# power.net
KiCad netlist of a schematic drawn in Altium Designer
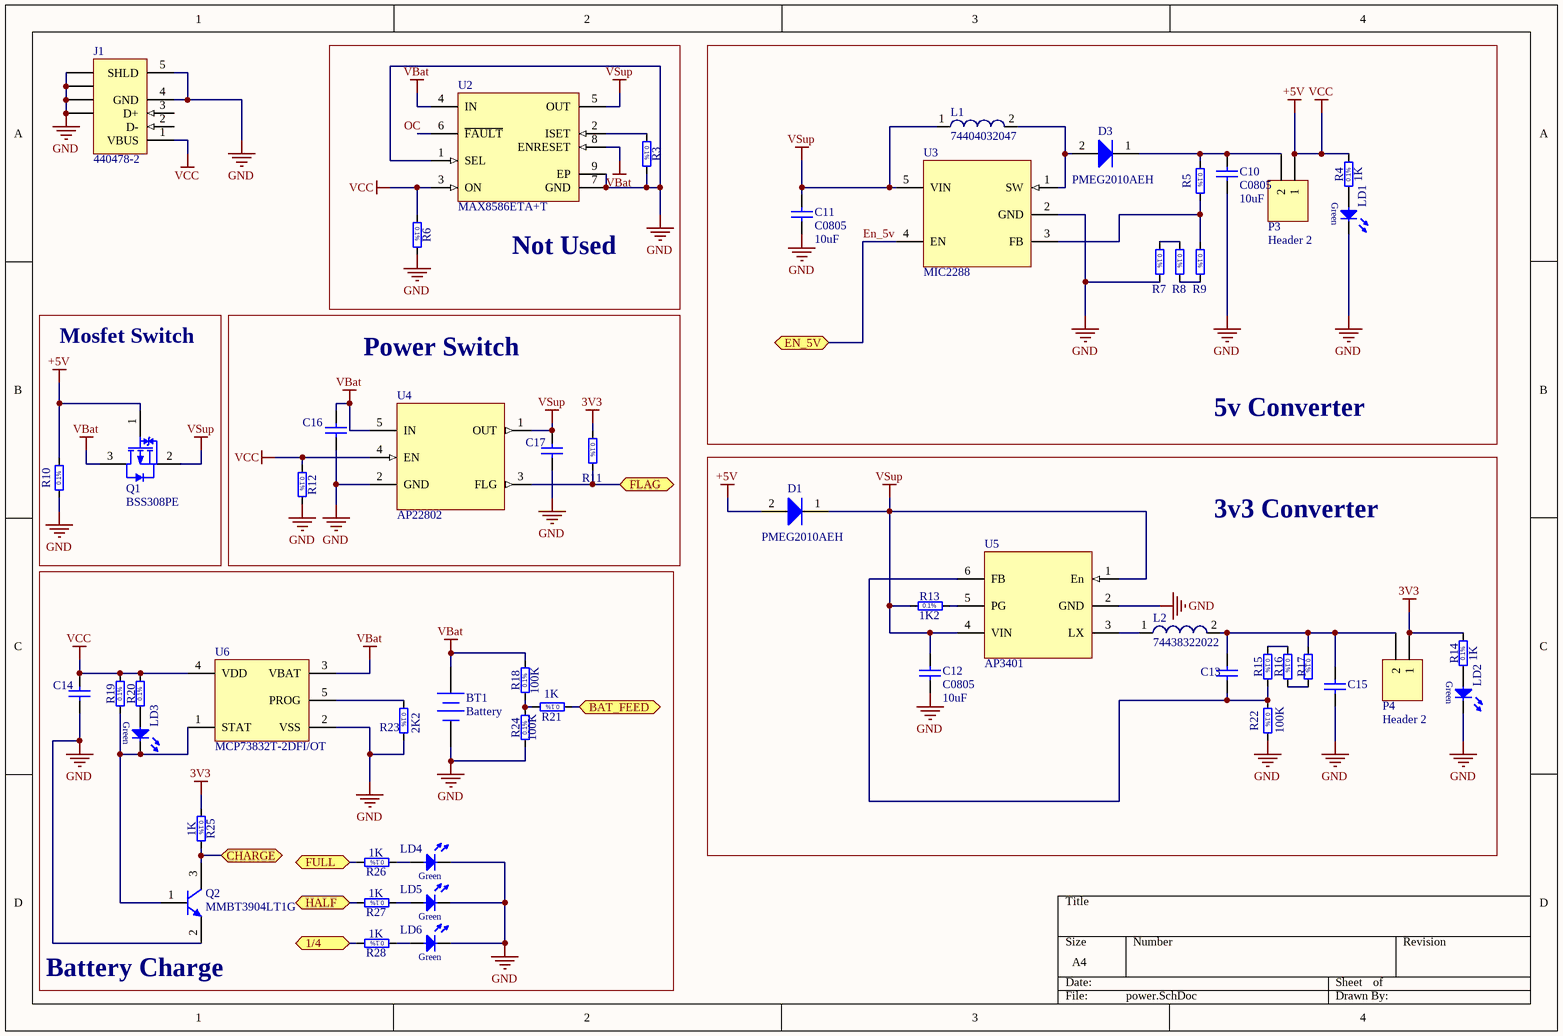
[diagram p0: power.SchDoc]

(export (version "E")
  (design (tool "Eeschema 10.0.6"))
  (components
    (comp (ref "BT1")
      (value "Battery")
      (footprint "BAT-2")
      (description "Multicell Battery")
      (fields (field (name "PUBLISHER") "Altium Limited"))
      (libsource (lib "Miscellaneous Devices") (part "Battery"))
    )
    (comp (ref "C10")
      (value "C0805")
      (footprint "0805")
      (description "Ceramic Chip Capacitor - Standard")
      (fields (field (name "ALTIUM_VALUE") "10uF") (field (name "PUBLISHER") "Altium Limited"))
      (libsource (lib "KEMET Chip Capacitor") (part "C0805"))
    )
    (comp (ref "C11")
      (value "C0805")
      (footprint "0805")
      (description "Ceramic Chip Capacitor - Standard")
      (fields (field (name "ALTIUM_VALUE") "10uF") (field (name "PUBLISHER") "Altium Limited"))
      (libsource (lib "KEMET Chip Capacitor") (part "C0805"))
    )
    (comp (ref "C12")
      (value "C0805")
      (footprint "0805")
      (description "Ceramic Chip Capacitor - Standard")
      (fields (field (name "ALTIUM_VALUE") "10uF") (field (name "PUBLISHER") "Altium Limited"))
      (libsource (lib "KEMET Chip Capacitor") (part "C0805"))
    )
    (comp (ref "C13")
      (value "C0805")
      (footprint "0805")
      (description "Ceramic Chip Capacitor - Standard")
      (fields (field (name "PUBLISHER") "Altium Limited"))
      (libsource (lib "KEMET Chip Capacitor") (part "C0805"))
    )
    (comp (ref "C14")
      (value "C0805")
      (footprint "0805")
      (description "Ceramic Chip Capacitor - Standard")
      (fields (field (name "PUBLISHER") "Altium Limited"))
      (libsource (lib "KEMET Chip Capacitor") (part "C0805"))
    )
    (comp (ref "C15")
      (value "C0805")
      (footprint "0805")
      (description "Ceramic Chip Capacitor - Standard")
      (fields (field (name "PUBLISHER") "Altium Limited"))
      (libsource (lib "KEMET Chip Capacitor") (part "C0805"))
    )
    (comp (ref "C16")
      (value "C0805")
      (footprint "0805")
      (description "Ceramic Chip Capacitor - Standard")
      (fields (field (name "PUBLISHER") "Altium Limited"))
      (libsource (lib "KEMET Chip Capacitor") (part "C0805"))
    )
    (comp (ref "C17")
      (value "C0805")
      (footprint "0805")
      (description "Ceramic Chip Capacitor - Standard")
      (fields (field (name "PUBLISHER") "Altium Limited"))
      (libsource (lib "KEMET Chip Capacitor") (part "C0805"))
    )
    (comp (ref "D1")
      (value "PMEG2010AEH")
      (footprint "ONSC-SOD-123-2-425-04_V")
      (description "Switching Diode, 2-Pin SOD-123, Pb-Free, Tape and Reel")
      (fields (field (name "MANUFACTURER") "On Semiconductor") (field (name "PARTNUMBER") "MMSD914T3G"))
      (libsource (lib "ON Semi Small Signal Switching Diodes") (part "MMSD914T3G"))
    )
    (comp (ref "D3")
      (value "PMEG2010AEH")
      (footprint "ONSC-SOD-123-2-425-04_V")
      (description "Switching Diode, 2-Pin SOD-123, Pb-Free, Tape and Reel")
      (fields (field (name "MANUFACTURER") "On Semiconductor") (field (name "PARTNUMBER") "MMSD914T3G"))
      (libsource (lib "ON Semi Small Signal Switching Diodes") (part "MMSD914T3G"))
    )
    (comp (ref "J1")
      (value "440478-2")
      (footprint "440478")
      (description "USB 2.0, Right Angle, SMT, A Type, Receptacle, 5 Position, Black")
      (fields (field (name "PUBLISHER") "Altium Limited"))
      (libsource (lib "AMP Serial Bus USB") (part "440478-2"))
    )
    (comp (ref "L1")
      (value "74404032047")
      (footprint "WE-LQS 3015")
      (description "WE-LQS SMD Power Inductor, L=4.7 µH")
      (libsource (lib "WE-LQS SMD Power Inductor") (part "74404032047"))
    )
    (comp (ref "L2")
      (value "74438322022")
      (footprint "SMD 2508")
      (description "Power Multilayer Inductor WE-MAPI, L=2.2µH")
      (libsource (lib "WE-MAPI SMD Power Inductor") (part "74438322022"))
    )
    (comp (ref "LD1")
      (value "Green")
      (footprint "LED_OSRAM_LGR971")
      (description "LED Green 1C 2A")
      (fields
        (field (name "PART NUMBER") "LED_OSRAM_LGR971")
        (field (name "MANUFACTURER") "OSRAM")
        (field (name "AUTHOR") "CERN DEM JLC")
      )
      (libsource (lib "ICs And Semiconductors") (part "LED Green 1C 2A"))
    )
    (comp (ref "LD2")
      (value "Green")
      (footprint "LED_OSRAM_LGR971")
      (description "LED Green 1C 2A")
      (fields
        (field (name "PART NUMBER") "LED_OSRAM_LGR971")
        (field (name "MANUFACTURER") "OSRAM")
        (field (name "AUTHOR") "CERN DEM JLC")
      )
      (libsource (lib "ICs And Semiconductors") (part "LED Green 1C 2A"))
    )
    (comp (ref "LD3")
      (value "Green")
      (footprint "LED_OSRAM_LGR971")
      (description "LED Green 1C 2A")
      (fields
        (field (name "PART NUMBER") "LED_OSRAM_LGR971")
        (field (name "MANUFACTURER") "OSRAM")
        (field (name "AUTHOR") "CERN DEM JLC")
      )
      (libsource (lib "ICs And Semiconductors") (part "LED Green 1C 2A"))
    )
    (comp (ref "LD4")
      (value "Green")
      (footprint "LED_OSRAM_LGR971")
      (description "LED Green 1C 2A")
      (fields
        (field (name "PART NUMBER") "LED_OSRAM_LGR971")
        (field (name "MANUFACTURER") "OSRAM")
        (field (name "AUTHOR") "CERN DEM JLC")
      )
      (libsource (lib "ICs And Semiconductors") (part "LED Green 1C 2A"))
    )
    (comp (ref "LD5")
      (value "Green")
      (footprint "LED_OSRAM_LGR971")
      (description "LED Green 1C 2A")
      (fields
        (field (name "PART NUMBER") "LED_OSRAM_LGR971")
        (field (name "MANUFACTURER") "OSRAM")
        (field (name "AUTHOR") "CERN DEM JLC")
      )
      (libsource (lib "ICs And Semiconductors") (part "LED Green 1C 2A"))
    )
    (comp (ref "LD6")
      (value "Green")
      (footprint "LED_OSRAM_LGR971")
      (description "LED Green 1C 2A")
      (fields
        (field (name "PART NUMBER") "LED_OSRAM_LGR971")
        (field (name "MANUFACTURER") "OSRAM")
        (field (name "AUTHOR") "CERN DEM JLC")
      )
      (libsource (lib "ICs And Semiconductors") (part "LED Green 1C 2A"))
    )
    (comp (ref "P3")
      (value "Header 2")
      (footprint "HDR1X2")
      (description "Header, 2-Pin")
      (fields (field (name "PUBLISHER") "Altium Limited"))
      (libsource (lib "Miscellaneous Connectors") (part "Header 2"))
    )
    (comp (ref "P4")
      (value "Header 2")
      (footprint "HDR1X2")
      (description "Header, 2-Pin")
      (fields (field (name "PUBLISHER") "Altium Limited"))
      (libsource (lib "Miscellaneous Connectors") (part "Header 2"))
    )
    (comp (ref "Q1")
      (value "BSS308PE")
      (footprint "INF-PG-SOT23_N")
      (fields (field (name "MANUFACTURER") "Infineon"))
      (libsource (lib "Infineon Power MOSFET") (part "BSS308PE"))
    )
    (comp (ref "Q2")
      (value "MMBT3904LT1G")
      (footprint "ONSC-SOT-23-3-318-08_V")
      (description "General Purpose Transistor, NPN Silicon, 3-Pin SOT-23, Pb-Free, Tape and Reel")
      (fields (field (name "MANUFACTURER") "On Semiconductor"))
      (libsource (lib "ON Semi General Purpose Transistors") (part "MMBT3904LT1G"))
    )
    (comp (ref "R3")
      (value "26K")
      (footprint "RESC2012X60N")
      (description "Resistor - 0.1%")
      (fields
        (field (name "PART NUMBER") "R0805_1K1_0.1%_0.1W_10PPM")
        (field (name "POWER") "0.1W")
        (field (name "AUTHOR") "CERN DEM JLC")
      )
      (libsource (lib "Resistors") (part "Resistor - 0.1%"))
    )
    (comp (ref "R4")
      (value "1K")
      (footprint "RESC2012X60N")
      (description "Resistor - 0.1%")
      (fields
        (field (name "PART NUMBER") "R0805_1K1_0.1%_0.1W_10PPM")
        (field (name "POWER") "0.1W")
        (field (name "AUTHOR") "CERN DEM JLC")
      )
      (libsource (lib "Resistors") (part "Resistor - 0.1%"))
    )
    (comp (ref "R5")
      (value "100K")
      (footprint "RESC2012X60N")
      (description "Resistor - 0.1%")
      (fields
        (field (name "PART NUMBER") "R0805_1K1_0.1%_0.1W_10PPM")
        (field (name "POWER") "0.1W")
        (field (name "AUTHOR") "CERN DEM JLC")
      )
      (libsource (lib "Resistors") (part "Resistor - 0.1%"))
    )
    (comp (ref "R6")
      (value "1K2")
      (footprint "RESC2012X60N")
      (description "Resistor - 0.1%")
      (fields
        (field (name "PART NUMBER") "R0805_1K1_0.1%_0.1W_10PPM")
        (field (name "POWER") "0.1W")
        (field (name "AUTHOR") "CERN DEM JLC")
      )
      (libsource (lib "Resistors") (part "Resistor - 0.1%"))
    )
    (comp (ref "R7")
      (value "10K")
      (footprint "RESC2012X60N")
      (description "Resistor - 0.1%")
      (fields
        (field (name "PART NUMBER") "R0805_1K1_0.1%_0.1W_10PPM")
        (field (name "POWER") "0.1W")
        (field (name "AUTHOR") "CERN DEM JLC")
      )
      (libsource (lib "Resistors") (part "Resistor - 0.1%"))
    )
    (comp (ref "R8")
      (value "1K")
      (footprint "RESC2012X60N")
      (description "Resistor - 0.1%")
      (fields
        (field (name "PART NUMBER") "R0805_1K1_0.1%_0.1W_10PPM")
        (field (name "POWER") "0.1W")
        (field (name "AUTHOR") "CERN DEM JLC")
      )
      (libsource (lib "Resistors") (part "Resistor - 0.1%"))
    )
    (comp (ref "R9")
      (value "100R")
      (footprint "RESC2012X60N")
      (description "Resistor - 0.1%")
      (fields
        (field (name "PART NUMBER") "R0805_1K1_0.1%_0.1W_10PPM")
        (field (name "POWER") "0.1W")
        (field (name "AUTHOR") "CERN DEM JLC")
      )
      (libsource (lib "Resistors") (part "Resistor - 0.1%"))
    )
    (comp (ref "R10")
      (value "1K2")
      (footprint "RESC2012X60N")
      (description "Resistor - 0.1%")
      (fields
        (field (name "PART NUMBER") "R0805_1K1_0.1%_0.1W_10PPM")
        (field (name "POWER") "0.1W")
        (field (name "AUTHOR") "CERN DEM JLC")
      )
      (libsource (lib "Resistors") (part "Resistor - 0.1%"))
    )
    (comp (ref "R11")
      (value "10K")
      (footprint "RESC2012X60N")
      (description "Resistor - 0.1%")
      (fields
        (field (name "PART NUMBER") "R0805_1K1_0.1%_0.1W_10PPM")
        (field (name "POWER") "0.1W")
        (field (name "AUTHOR") "CERN DEM JLC")
      )
      (libsource (lib "Resistors") (part "Resistor - 0.1%"))
    )
    (comp (ref "R12")
      (value "1K2")
      (footprint "RESC2012X60N")
      (description "Resistor - 0.1%")
      (fields
        (field (name "PART NUMBER") "R0805_1K1_0.1%_0.1W_10PPM")
        (field (name "POWER") "0.1W")
        (field (name "AUTHOR") "CERN DEM JLC")
      )
      (libsource (lib "Resistors") (part "Resistor - 0.1%"))
    )
    (comp (ref "R13")
      (value "1K2")
      (footprint "RESC2012X60N")
      (description "Resistor - 0.1%")
      (fields
        (field (name "PART NUMBER") "R0805_1K1_0.1%_0.1W_10PPM")
        (field (name "POWER") "0.1W")
        (field (name "AUTHOR") "CERN DEM JLC")
      )
      (libsource (lib "Resistors") (part "Resistor - 0.1%"))
    )
    (comp (ref "R14")
      (value "1K")
      (footprint "RESC2012X60N")
      (description "Resistor - 0.1%")
      (fields
        (field (name "PART NUMBER") "R0805_1K1_0.1%_0.1W_10PPM")
        (field (name "POWER") "0.1W")
        (field (name "AUTHOR") "CERN DEM JLC")
      )
      (libsource (lib "Resistors") (part "Resistor - 0.1%"))
    )
    (comp (ref "R15")
      (value "RC0805FR-07430KL")
      (footprint "RESC2012X60N")
      (description "Resistor - 0.1%")
      (fields
        (field (name "PART NUMBER") "R0805_1K1_0.1%_0.1W_10PPM")
        (field (name "POWER") "0.1W")
        (field (name "AUTHOR") "CERN DEM JLC")
      )
      (libsource (lib "Resistors") (part "Resistor - 0.1%"))
    )
    (comp (ref "R16")
      (value "150K")
      (footprint "RESC2012X60N")
      (description "Resistor - 0.1%")
      (fields
        (field (name "PART NUMBER") "R0805_1K1_0.1%_0.1W_10PPM")
        (field (name "POWER") "0.1W")
        (field (name "AUTHOR") "CERN DEM JLC")
      )
      (libsource (lib "Resistors") (part "Resistor - 0.1%"))
    )
    (comp (ref "R17")
      (value "150K")
      (footprint "RESC2012X60N")
      (description "Resistor - 0.1%")
      (fields
        (field (name "PART NUMBER") "R0805_1K1_0.1%_0.1W_10PPM")
        (field (name "POWER") "0.1W")
        (field (name "AUTHOR") "CERN DEM JLC")
      )
      (libsource (lib "Resistors") (part "Resistor - 0.1%"))
    )
    (comp (ref "R18")
      (value "100K")
      (footprint "RESC2012X60N")
      (description "Resistor - 0.1%")
      (fields
        (field (name "PART NUMBER") "R0805_1K1_0.1%_0.1W_10PPM")
        (field (name "POWER") "0.1W")
        (field (name "AUTHOR") "CERN DEM JLC")
      )
      (libsource (lib "Resistors") (part "Resistor - 0.1%"))
    )
    (comp (ref "R19")
      (value "1K")
      (footprint "RESC2012X60N")
      (description "Resistor - 0.1%")
      (fields
        (field (name "PART NUMBER") "R0805_1K1_0.1%_0.1W_10PPM")
        (field (name "POWER") "0.1W")
        (field (name "AUTHOR") "CERN DEM JLC")
      )
      (libsource (lib "Resistors") (part "Resistor - 0.1%"))
    )
    (comp (ref "R20")
      (value "1K")
      (footprint "RESC2012X60N")
      (description "Resistor - 0.1%")
      (fields
        (field (name "PART NUMBER") "R0805_1K1_0.1%_0.1W_10PPM")
        (field (name "POWER") "0.1W")
        (field (name "AUTHOR") "CERN DEM JLC")
      )
      (libsource (lib "Resistors") (part "Resistor - 0.1%"))
    )
    (comp (ref "R21")
      (value "1K")
      (footprint "RESC2012X60N")
      (description "Resistor - 0.1%")
      (fields
        (field (name "PART NUMBER") "R0805_1K1_0.1%_0.1W_10PPM")
        (field (name "POWER") "0.1W")
        (field (name "AUTHOR") "CERN DEM JLC")
      )
      (libsource (lib "Resistors") (part "Resistor - 0.1%"))
    )
    (comp (ref "R22")
      (value "100K")
      (footprint "RESC2012X60N")
      (description "Resistor - 0.1%")
      (fields
        (field (name "PART NUMBER") "R0805_1K1_0.1%_0.1W_10PPM")
        (field (name "POWER") "0.1W")
        (field (name "AUTHOR") "CERN DEM JLC")
      )
      (libsource (lib "Resistors") (part "Resistor - 0.1%"))
    )
    (comp (ref "R23")
      (value "2K2")
      (footprint "RESC2012X60N")
      (description "Resistor - 0.1%")
      (fields
        (field (name "PART NUMBER") "R0805_1K1_0.1%_0.1W_10PPM")
        (field (name "POWER") "0.1W")
        (field (name "AUTHOR") "CERN DEM JLC")
      )
      (libsource (lib "Resistors") (part "Resistor - 0.1%"))
    )
    (comp (ref "R24")
      (value "100K")
      (footprint "RESC2012X60N")
      (description "Resistor - 0.1%")
      (fields
        (field (name "PART NUMBER") "R0805_1K1_0.1%_0.1W_10PPM")
        (field (name "POWER") "0.1W")
        (field (name "AUTHOR") "CERN DEM JLC")
      )
      (libsource (lib "Resistors") (part "Resistor - 0.1%"))
    )
    (comp (ref "R25")
      (value "1K")
      (footprint "RESC2012X60N")
      (description "Resistor - 0.1%")
      (fields
        (field (name "PART NUMBER") "R0805_1K1_0.1%_0.1W_10PPM")
        (field (name "POWER") "0.1W")
        (field (name "AUTHOR") "CERN DEM JLC")
      )
      (libsource (lib "Resistors") (part "Resistor - 0.1%"))
    )
    (comp (ref "R26")
      (value "1K")
      (footprint "RESC2012X60N")
      (description "Resistor - 0.1%")
      (fields
        (field (name "PART NUMBER") "R0805_1K1_0.1%_0.1W_10PPM")
        (field (name "POWER") "0.1W")
        (field (name "AUTHOR") "CERN DEM JLC")
      )
      (libsource (lib "Resistors") (part "Resistor - 0.1%"))
    )
    (comp (ref "R27")
      (value "1K")
      (footprint "RESC2012X60N")
      (description "Resistor - 0.1%")
      (fields
        (field (name "PART NUMBER") "R0805_1K1_0.1%_0.1W_10PPM")
        (field (name "POWER") "0.1W")
        (field (name "AUTHOR") "CERN DEM JLC")
      )
      (libsource (lib "Resistors") (part "Resistor - 0.1%"))
    )
    (comp (ref "R28")
      (value "1K")
      (footprint "RESC2012X60N")
      (description "Resistor - 0.1%")
      (fields
        (field (name "PART NUMBER") "R0805_1K1_0.1%_0.1W_10PPM")
        (field (name "POWER") "0.1W")
        (field (name "AUTHOR") "CERN DEM JLC")
      )
      (libsource (lib "Resistors") (part "Resistor - 0.1%"))
    )
    (comp (ref "U2")
      (value "MAX8586ETA+T")
      (footprint "T833+2")
      (description "Single 1.2A USB Switch, 8-Pin TDFN, -40°C to +85°C, Pb-Free, Tape and Reel")
      (libsource (lib "Maxim Hot-Swap, PoE and Power Switching") (part "MAX8586ETA+T"))
    )
    (comp (ref "U3") (value "MIC2288") (footprint "TSOT25") (libsource (lib "Microchip") (part "MIC2288")))
    (comp (ref "U4")
      (value "AP22802")
      (footprint "TSOT25")
      (libsource (lib "Diodes Incorporated") (part "AP22802"))
    )
    (comp (ref "U5")
      (value "AP3401")
      (footprint "TSOT26")
      (libsource (lib "Diodes Incorporated") (part "AP3401"))
    )
    (comp (ref "U6")
      (value "MCP73832T-2DFI/OT")
      (footprint "SOT-23-OT5_N")
      (fields (field (name "MANUFACTURER") "Microchip"))
      (libsource (lib "Microchip Power Management Battery Management") (part "MCP73832T-2DFI/OT"))
    )
  )
  (nets
    (net (code "1") (name "+5V") (class "Default")
      (node (ref "C14") (pin "2") (pinfunction "2_2") (pintype "passive"))
      (node (ref "D1") (pin "2") (pinfunction "A_2") (pintype "passive"))
      (node (ref "J1") (pin "1") (pinfunction "VBUS_1") (pintype "power_in"))
      (node (ref "P3") (pin "1") (pinfunction "1_1") (pintype "passive"))
      (node (ref "Q1") (pin "1") (pinfunction "GATE_1") (pintype "passive"))
      (node (ref "R10") (pin "2") (pinfunction "2_2") (pintype "passive"))
      (node (ref "R12") (pin "1") (pinfunction "1_1") (pintype "passive"))
      (node (ref "R19") (pin "2") (pinfunction "2_2") (pintype "passive"))
      (node (ref "R20") (pin "2") (pinfunction "2_2") (pintype "passive"))
      (node (ref "R4") (pin "2") (pinfunction "2_2") (pintype "passive"))
      (node (ref "R6") (pin "1") (pinfunction "1_1") (pintype "passive"))
      (node (ref "U2") (pin "3") (pinfunction "ON_3") (pintype "input"))
      (node (ref "U4") (pin "4") (pinfunction "EN_4") (pintype "input"))
      (node (ref "U6") (pin "4") (pinfunction "VDD_4") (pintype "power_in"))
    )
    (net (code "2") (name "/1{slash}4") (class "Default")
      (node (ref "R28") (pin "2") (pinfunction "2_2") (pintype "passive"))
    )
    (net (code "3") (name "/BAT_FEED") (class "Default")
      (node (ref "R21") (pin "1") (pinfunction "1_1") (pintype "passive"))
    )
    (net (code "4") (name "/CHARGE") (class "Default")
      (node (ref "Q2") (pin "3") (pinfunction "C_3") (pintype "passive"))
      (node (ref "R25") (pin "2") (pinfunction "2_2") (pintype "passive"))
    )
    (net (code "5") (name "/En_5v") (class "Default")
      (node (ref "U3") (pin "4") (pinfunction "EN_4") (pintype "power_in"))
    )
    (net (code "6") (name "/FLAG") (class "Default")
      (node (ref "R11") (pin "2") (pinfunction "2_2") (pintype "passive"))
      (node (ref "U4") (pin "3") (pinfunction "FLG_3") (pintype "output"))
    )
    (net (code "7") (name "/FULL") (class "Default")
      (node (ref "R26") (pin "2") (pinfunction "2_2") (pintype "passive"))
    )
    (net (code "8") (name "/HALF") (class "Default")
      (node (ref "R27") (pin "2") (pinfunction "2_2") (pintype "passive"))
    )
    (net (code "10") (name "3V3") (class "Default")
      (node (ref "P4") (pin "1") (pinfunction "1_1") (pintype "passive"))
      (node (ref "R11") (pin "1") (pinfunction "1_1") (pintype "passive"))
      (node (ref "R14") (pin "2") (pinfunction "2_2") (pintype "passive"))
      (node (ref "R25") (pin "1") (pinfunction "1_1") (pintype "passive"))
    )
    (net (code "11") (name "GND") (class "Default")
      (node (ref "BT1") (pin "2") (pinfunction "-_2") (pintype "passive"))
      (node (ref "C10") (pin "1") (pinfunction "1_1") (pintype "passive"))
      (node (ref "C11") (pin "1") (pinfunction "1_1") (pintype "passive"))
      (node (ref "C12") (pin "1") (pinfunction "1_1") (pintype "passive"))
      (node (ref "C14") (pin "1") (pinfunction "1_1") (pintype "passive"))
      (node (ref "C15") (pin "1") (pinfunction "1_1") (pintype "passive"))
      (node (ref "C16") (pin "2") (pinfunction "2_2") (pintype "passive"))
      (node (ref "C17") (pin "1") (pinfunction "1_1") (pintype "passive"))
      (node (ref "J1") (pin "4") (pinfunction "GND_4") (pintype "power_in"))
      (node (ref "J1") (pin "5") (pinfunction "SHLD_5") (pintype "passive"))
      (node (ref "J1") (pin "6") (pinfunction "SHLD_6") (pintype "passive"))
      (node (ref "J1") (pin "7") (pinfunction "SHLD_7") (pintype "passive"))
      (node (ref "J1") (pin "8") (pinfunction "SHLD_8") (pintype "passive"))
      (node (ref "J1") (pin "9") (pinfunction "SHLD_9") (pintype "passive"))
      (node (ref "LD1") (pin "1") (pinfunction "C_1") (pintype "passive"))
      (node (ref "LD2") (pin "1") (pinfunction "C_1") (pintype "passive"))
      (node (ref "LD4") (pin "1") (pinfunction "C_1") (pintype "passive"))
      (node (ref "LD5") (pin "1") (pinfunction "C_1") (pintype "passive"))
      (node (ref "LD6") (pin "1") (pinfunction "C_1") (pintype "passive"))
      (node (ref "Q2") (pin "2") (pinfunction "E_2") (pintype "passive"))
      (node (ref "R10") (pin "1") (pinfunction "1_1") (pintype "passive"))
      (node (ref "R12") (pin "2") (pinfunction "2_2") (pintype "passive"))
      (node (ref "R22") (pin "2") (pinfunction "2_2") (pintype "passive"))
      (node (ref "R23") (pin "2") (pinfunction "2_2") (pintype "passive"))
      (node (ref "R24") (pin "1") (pinfunction "1_1") (pintype "passive"))
      (node (ref "R3") (pin "2") (pinfunction "2_2") (pintype "passive"))
      (node (ref "R6") (pin "2") (pinfunction "2_2") (pintype "passive"))
      (node (ref "R7") (pin "2") (pinfunction "2_2") (pintype "passive"))
      (node (ref "U2") (pin "1") (pinfunction "SEL_1") (pintype "input"))
      (node (ref "U2") (pin "7") (pinfunction "GND_7") (pintype "power_in"))
      (node (ref "U2") (pin "9") (pinfunction "EP_9") (pintype "power_in"))
      (node (ref "U3") (pin "2") (pinfunction "GND_2") (pintype "power_in"))
      (node (ref "U4") (pin "2") (pinfunction "GND_2") (pintype "power_in"))
      (node (ref "U5") (pin "2") (pinfunction "GND_2") (pintype "power_in"))
      (node (ref "U6") (pin "2") (pinfunction "VSS_2") (pintype "power_in"))
    )
    (net (code "12") (name "Net-(C13-Pad2)") (class "Default")
      (node (ref "C13") (pin "2") (pinfunction "2_2") (pintype "passive"))
      (node (ref "C15") (pin "2") (pinfunction "2_2") (pintype "passive"))
      (node (ref "L2") (pin "2") (pinfunction "2_2") (pintype "passive"))
      (node (ref "P4") (pin "2") (pinfunction "2_2") (pintype "passive"))
      (node (ref "R17") (pin "1") (pinfunction "1_1") (pintype "passive"))
    )
    (net (code "13") (name "Net-(D3-A)") (class "Default")
      (node (ref "D3") (pin "2") (pinfunction "A_2") (pintype "passive"))
      (node (ref "L1") (pin "2") (pinfunction "2_2") (pintype "passive"))
      (node (ref "U3") (pin "1") (pinfunction "SW_1") (pintype "input"))
    )
    (net (code "14") (name "Net-(D3-K)") (class "Default")
      (node (ref "C10") (pin "2") (pinfunction "2_2") (pintype "passive"))
      (node (ref "D3") (pin "1") (pinfunction "K_1") (pintype "passive"))
      (node (ref "P3") (pin "2") (pinfunction "2_2") (pintype "passive"))
      (node (ref "R5") (pin "1") (pinfunction "1_1") (pintype "passive"))
    )
    (net (code "15") (name "Net-(LD1-A)") (class "Default")
      (node (ref "LD1") (pin "2") (pinfunction "A_2") (pintype "passive"))
      (node (ref "R4") (pin "1") (pinfunction "1_1") (pintype "passive"))
    )
    (net (code "16") (name "Net-(LD2-A)") (class "Default")
      (node (ref "LD2") (pin "2") (pinfunction "A_2") (pintype "passive"))
      (node (ref "R14") (pin "1") (pinfunction "1_1") (pintype "passive"))
    )
    (net (code "17") (name "Net-(LD3-A)") (class "Default")
      (node (ref "LD3") (pin "2") (pinfunction "A_2") (pintype "passive"))
      (node (ref "R20") (pin "1") (pinfunction "1_1") (pintype "passive"))
    )
    (net (code "18") (name "Net-(LD3-C)") (class "Default")
      (node (ref "LD3") (pin "1") (pinfunction "C_1") (pintype "passive"))
      (node (ref "Q2") (pin "1") (pinfunction "B_1") (pintype "passive"))
      (node (ref "R19") (pin "1") (pinfunction "1_1") (pintype "passive"))
      (node (ref "U6") (pin "1") (pinfunction "STAT_1") (pintype "open_collector"))
    )
    (net (code "19") (name "Net-(LD4-A)") (class "Default")
      (node (ref "LD4") (pin "2") (pinfunction "A_2") (pintype "passive"))
      (node (ref "R26") (pin "1") (pinfunction "1_1") (pintype "passive"))
    )
    (net (code "20") (name "Net-(LD5-A)") (class "Default")
      (node (ref "LD5") (pin "2") (pinfunction "A_2") (pintype "passive"))
      (node (ref "R27") (pin "1") (pinfunction "1_1") (pintype "passive"))
    )
    (net (code "21") (name "Net-(LD6-A)") (class "Default")
      (node (ref "LD6") (pin "2") (pinfunction "A_2") (pintype "passive"))
      (node (ref "R28") (pin "1") (pinfunction "1_1") (pintype "passive"))
    )
    (net (code "22") (name "Net-(R7-Pad1)") (class "Default")
      (node (ref "R7") (pin "1") (pinfunction "1_1") (pintype "passive"))
      (node (ref "R8") (pin "1") (pinfunction "1_1") (pintype "passive"))
    )
    (net (code "23") (name "Net-(R8-Pad2)") (class "Default")
      (node (ref "R8") (pin "2") (pinfunction "2_2") (pintype "passive"))
      (node (ref "R9") (pin "2") (pinfunction "2_2") (pintype "passive"))
    )
    (net (code "24") (name "Net-(R15-Pad1)") (class "Default")
      (node (ref "R15") (pin "1") (pinfunction "1_1") (pintype "passive"))
      (node (ref "R16") (pin "1") (pinfunction "1_1") (pintype "passive"))
    )
    (net (code "25") (name "Net-(R16-Pad2)") (class "Default")
      (node (ref "R16") (pin "2") (pinfunction "2_2") (pintype "passive"))
      (node (ref "R17") (pin "2") (pinfunction "2_2") (pintype "passive"))
    )
    (net (code "26") (name "Net-(R18-Pad1)") (class "Default")
      (node (ref "R18") (pin "1") (pinfunction "1_1") (pintype "passive"))
      (node (ref "R21") (pin "2") (pinfunction "2_2") (pintype "passive"))
      (node (ref "R24") (pin "2") (pinfunction "2_2") (pintype "passive"))
    )
    (net (code "27") (name "Net-(U2-ISET)") (class "Default")
      (node (ref "R3") (pin "1") (pinfunction "1_1") (pintype "passive"))
      (node (ref "U2") (pin "2") (pinfunction "ISET_2") (pintype "input"))
    )
    (net (code "28") (name "Net-(U3-FB)") (class "Default")
      (node (ref "R5") (pin "2") (pinfunction "2_2") (pintype "passive"))
      (node (ref "R9") (pin "1") (pinfunction "1_1") (pintype "passive"))
      (node (ref "U3") (pin "3") (pinfunction "FB_3") (pintype "passive"))
    )
    (net (code "29") (name "Net-(U5-FB)") (class "Default")
      (node (ref "C13") (pin "1") (pinfunction "1_1") (pintype "passive"))
      (node (ref "R15") (pin "2") (pinfunction "2_2") (pintype "passive"))
      (node (ref "R22") (pin "1") (pinfunction "1_1") (pintype "passive"))
      (node (ref "U5") (pin "6") (pinfunction "FB_6") (pintype "passive"))
    )
    (net (code "30") (name "Net-(U5-LX)") (class "Default")
      (node (ref "L2") (pin "1") (pinfunction "1_1") (pintype "passive"))
      (node (ref "U5") (pin "3") (pinfunction "LX_3") (pintype "passive"))
    )
    (net (code "31") (name "Net-(U5-PG)") (class "Default")
      (node (ref "R13") (pin "1") (pinfunction "1_1") (pintype "passive"))
      (node (ref "U5") (pin "5") (pinfunction "PG_5") (pintype "open_collector"))
    )
    (net (code "32") (name "Net-(U6-PROG)") (class "Default")
      (node (ref "R23") (pin "1") (pinfunction "1_1") (pintype "passive"))
      (node (ref "U6") (pin "5") (pinfunction "PROG_5") (pintype "passive"))
    )
    (net (code "33") (name "VBat") (class "Default")
      (node (ref "BT1") (pin "1") (pinfunction "+_1") (pintype "passive"))
      (node (ref "C16") (pin "1") (pinfunction "1_1") (pintype "passive"))
      (node (ref "Q1") (pin "3") (pinfunction "DRAIN_3") (pintype "passive"))
      (node (ref "R18") (pin "2") (pinfunction "2_2") (pintype "passive"))
      (node (ref "U2") (pin "4") (pinfunction "IN_4") (pintype "power_in"))
      (node (ref "U2") (pin "8") (pinfunction "ENRESET_8") (pintype "input"))
      (node (ref "U4") (pin "5") (pinfunction "IN_5") (pintype "power_in"))
      (node (ref "U6") (pin "3") (pinfunction "VBAT_3") (pintype "power_in"))
    )
    (net (code "34") (name "VSup") (class "Default")
      (node (ref "C11") (pin "2") (pinfunction "2_2") (pintype "passive"))
      (node (ref "C12") (pin "2") (pinfunction "2_2") (pintype "passive"))
      (node (ref "C17") (pin "2") (pinfunction "2_2") (pintype "passive"))
      (node (ref "D1") (pin "1") (pinfunction "K_1") (pintype "passive"))
      (node (ref "L1") (pin "1") (pinfunction "1_1") (pintype "passive"))
      (node (ref "Q1") (pin "2") (pinfunction "SOURCE_2") (pintype "passive"))
      (node (ref "R13") (pin "2") (pinfunction "2_2") (pintype "passive"))
      (node (ref "U2") (pin "5") (pinfunction "OUT_5") (pintype "power_in"))
      (node (ref "U3") (pin "5") (pinfunction "VIN_5") (pintype "passive"))
      (node (ref "U4") (pin "1") (pinfunction "OUT_1") (pintype "output"))
      (node (ref "U5") (pin "1") (pinfunction "En_1") (pintype "input"))
      (node (ref "U5") (pin "4") (pinfunction "VIN_4") (pintype "power_in"))
    )
    (net (code "35") (name "unconnected-(J1-D+-Pad3)") (class "Default")
      (node (ref "J1") (pin "3") (pinfunction "D+_3") (pintype "input"))
    )
    (net (code "36") (name "unconnected-(J1-D--Pad2)") (class "Default")
      (node (ref "J1") (pin "2") (pinfunction "D-_2") (pintype "input"))
    )
    (net (code "37") (name "unconnected-(U2-~{FAULT}-Pad6)") (class "Default")
      (node (ref "U2") (pin "6") (pinfunction "~{FAULT}_6") (pintype "open_collector"))
    )
  )
)
